# LED_Driver.net
KiCad netlist of a schematic drawn in Altium Designer
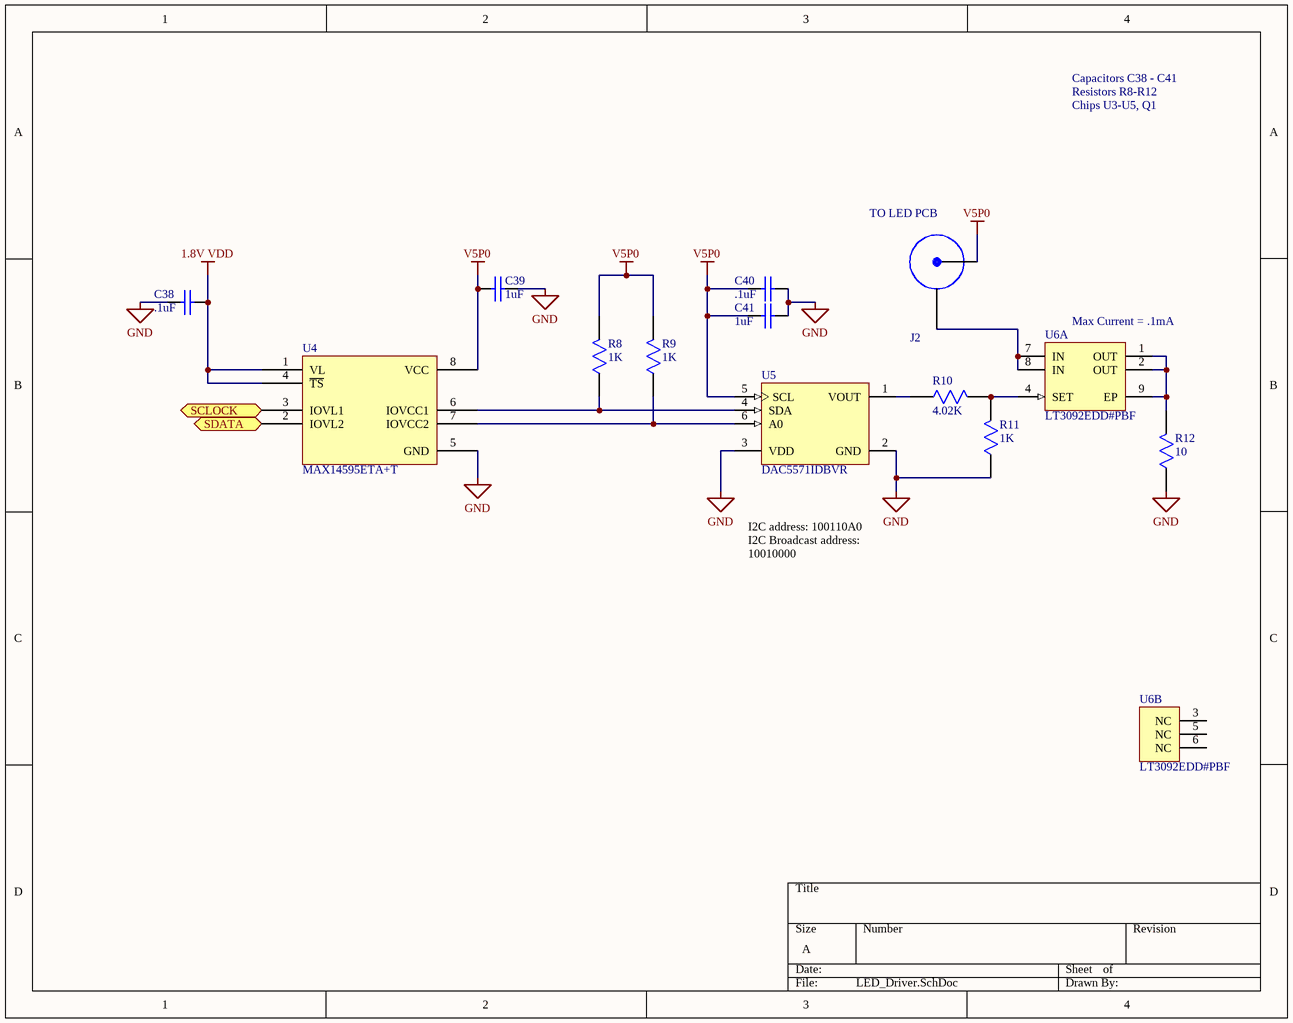
[diagram p0: LED_Driver.SchDoc]

(export (version "E")
  (design (tool "Eeschema 10.0.6"))
  (components
    (comp (ref "C38")
      (value ".1uF")
      (footprint "SMD CAP 0402")
      (libsource (lib "DA_Component_Library") (part "Capacitor"))
    )
    (comp (ref "C39")
      (value "1uF")
      (footprint "SMD CAP 0402")
      (libsource (lib "DA_Component_Library") (part "Capacitor"))
    )
    (comp (ref "C40")
      (value ".1uF")
      (footprint "SMD CAP 0402")
      (libsource (lib "DA_Component_Library") (part "Capacitor"))
    )
    (comp (ref "C41")
      (value "1uF")
      (footprint "SMD CAP 0402")
      (libsource (lib "DA_Component_Library") (part "Capacitor"))
    )
    (comp (ref "J2")
      (value "Coax Connector")
      (footprint "Coax Direct Solder ThroughHoles")
      (libsource (lib "DA_Component_Library") (part "Coax Connector"))
    )
    (comp (ref "R8")
      (value "1K")
      (footprint "SMD RES 0402")
      (libsource (lib "DA_Component_Library") (part "Resistor"))
    )
    (comp (ref "R9")
      (value "1K")
      (footprint "SMD RES 0402")
      (libsource (lib "DA_Component_Library") (part "Resistor"))
    )
    (comp (ref "R10")
      (value "4.02K")
      (footprint "SMD RES 0402")
      (libsource (lib "DA_Component_Library") (part "Resistor"))
    )
    (comp (ref "R11")
      (value "1K")
      (footprint "SMD RES 0402")
      (libsource (lib "DA_Component_Library") (part "Resistor"))
    )
    (comp (ref "R12")
      (value "10")
      (footprint "SMD RES 0402")
      (libsource (lib "DA_Component_Library") (part "Resistor"))
    )
    (comp (ref "U4")
      (value "MAX14595ETA+T")
      (footprint "8 TDFN")
      (description "Level Translator")
      (libsource (lib "Miniscope") (part "MAX14595ETA+T"))
    )
    (comp (ref "U5")
      (value "DAC5571IDBVR")
      (footprint "TI-DBV6_M")
      (fields (field (name "MANUFACTURER") "Texas Instruments"))
      (libsource (lib "DA_Component_Library") (part "DAC5571IDBVR"))
    )
    (comp (ref "U6")
      (value "LT3092EDD#PBF")
      (footprint "LT-DD-8_V")
      (fields (field (name "MANUFACTURER") "Linear Technology"))
      (libsource (lib "DA_Component_Library") (part "LT3092EDD#PBF"))
    )
  )
  (nets
    (net (code "1") (name "/SCLOCK") (class "Default")
      (node (ref "U4") (pin "3") (pinfunction "IOVL1_3") (pintype "passive"))
    )
    (net (code "2") (name "/SDATA") (class "Default")
      (node (ref "U4") (pin "2") (pinfunction "IOVL2_2") (pintype "passive"))
    )
    (net (code "3") (name "1.8V VDD") (class "Default")
      (node (ref "C38") (pin "1") (pinfunction "1_1") (pintype "passive"))
      (node (ref "U4") (pin "1") (pinfunction "VL_1") (pintype "passive"))
      (node (ref "U4") (pin "4") (pinfunction "~{TS}_4") (pintype "passive"))
    )
    (net (code "4") (name "GND") (class "Default")
      (node (ref "C38") (pin "0") (pinfunction "0_0") (pintype "passive"))
      (node (ref "C39") (pin "1") (pinfunction "1_1") (pintype "passive"))
      (node (ref "C40") (pin "1") (pinfunction "1_1") (pintype "passive"))
      (node (ref "C41") (pin "1") (pinfunction "1_1") (pintype "passive"))
      (node (ref "R11") (pin "0") (pinfunction "0_0") (pintype "passive"))
      (node (ref "R12") (pin "0") (pinfunction "0_0") (pintype "passive"))
      (node (ref "U4") (pin "5") (pinfunction "GND_5") (pintype "passive"))
      (node (ref "U5") (pin "2") (pinfunction "GND_2") (pintype "power_in"))
      (node (ref "U5") (pin "3") (pinfunction "VDD_3") (pintype "power_in"))
    )
    (net (code "5") (name "Net-(J2-Pad1)") (class "Default")
      (node (ref "J2") (pin "1") (pinfunction "1_1") (pintype "passive"))
      (node (ref "U6") (pin "7") (pinfunction "IN_7") (pintype "power_in"))
      (node (ref "U6") (pin "8") (pinfunction "IN_8") (pintype "power_in"))
    )
    (net (code "6") (name "Net-(U4-IOVCC1)") (class "Default")
      (node (ref "R8") (pin "0") (pinfunction "0_0") (pintype "passive"))
      (node (ref "U4") (pin "6") (pinfunction "IOVCC1_6") (pintype "passive"))
      (node (ref "U5") (pin "4") (pinfunction "SDA_4") (pintype "input"))
    )
    (net (code "7") (name "Net-(U4-IOVCC2)") (class "Default")
      (node (ref "R9") (pin "0") (pinfunction "0_0") (pintype "passive"))
      (node (ref "U4") (pin "7") (pinfunction "IOVCC2_7") (pintype "passive"))
      (node (ref "U5") (pin "6") (pinfunction "A0_6") (pintype "input"))
    )
    (net (code "8") (name "Net-(U5-VOUT)") (class "Default")
      (node (ref "R10") (pin "0") (pinfunction "0_0") (pintype "passive"))
      (node (ref "U5") (pin "1") (pinfunction "VOUT_1") (pintype "tri_state"))
    )
    (net (code "9") (name "Net-(U6A-EP)") (class "Default")
      (node (ref "R12") (pin "1") (pinfunction "1_1") (pintype "passive"))
      (node (ref "U6") (pin "1") (pinfunction "OUT_1") (pintype "power_in"))
      (node (ref "U6") (pin "2") (pinfunction "OUT_2") (pintype "power_in"))
      (node (ref "U6") (pin "9") (pinfunction "EP_9") (pintype "power_in"))
    )
    (net (code "10") (name "Net-(U6A-SET)") (class "Default")
      (node (ref "R10") (pin "1") (pinfunction "1_1") (pintype "passive"))
      (node (ref "R11") (pin "1") (pinfunction "1_1") (pintype "passive"))
      (node (ref "U6") (pin "4") (pinfunction "SET_4") (pintype "input"))
    )
    (net (code "11") (name "V5P0") (class "Default")
      (node (ref "C39") (pin "0") (pinfunction "0_0") (pintype "passive"))
      (node (ref "C40") (pin "0") (pinfunction "0_0") (pintype "passive"))
      (node (ref "C41") (pin "0") (pinfunction "0_0") (pintype "passive"))
      (node (ref "J2") (pin "0") (pinfunction "0_0") (pintype "passive"))
      (node (ref "R8") (pin "1") (pinfunction "1_1") (pintype "passive"))
      (node (ref "R9") (pin "1") (pinfunction "1_1") (pintype "passive"))
      (node (ref "U4") (pin "8") (pinfunction "VCC_8") (pintype "passive"))
      (node (ref "U5") (pin "5") (pinfunction "SCL_5") (pintype "input"))
    )
    (net (code "12") (name "unconnected-(U6B-NC-Pad3)") (class "Default")
      (node (ref "U6") (pin "3") (pinfunction "NC_3") (pintype "passive"))
    )
    (net (code "13") (name "unconnected-(U6B-NC-Pad5)") (class "Default")
      (node (ref "U6") (pin "5") (pinfunction "NC_5") (pintype "passive"))
    )
    (net (code "14") (name "unconnected-(U6B-NC-Pad6)") (class "Default")
      (node (ref "U6") (pin "6") (pinfunction "NC_6") (pintype "passive"))
    )
  )
)
